# REIS_PCB.net
KiCad netlist of a schematic drawn in Altium Designer
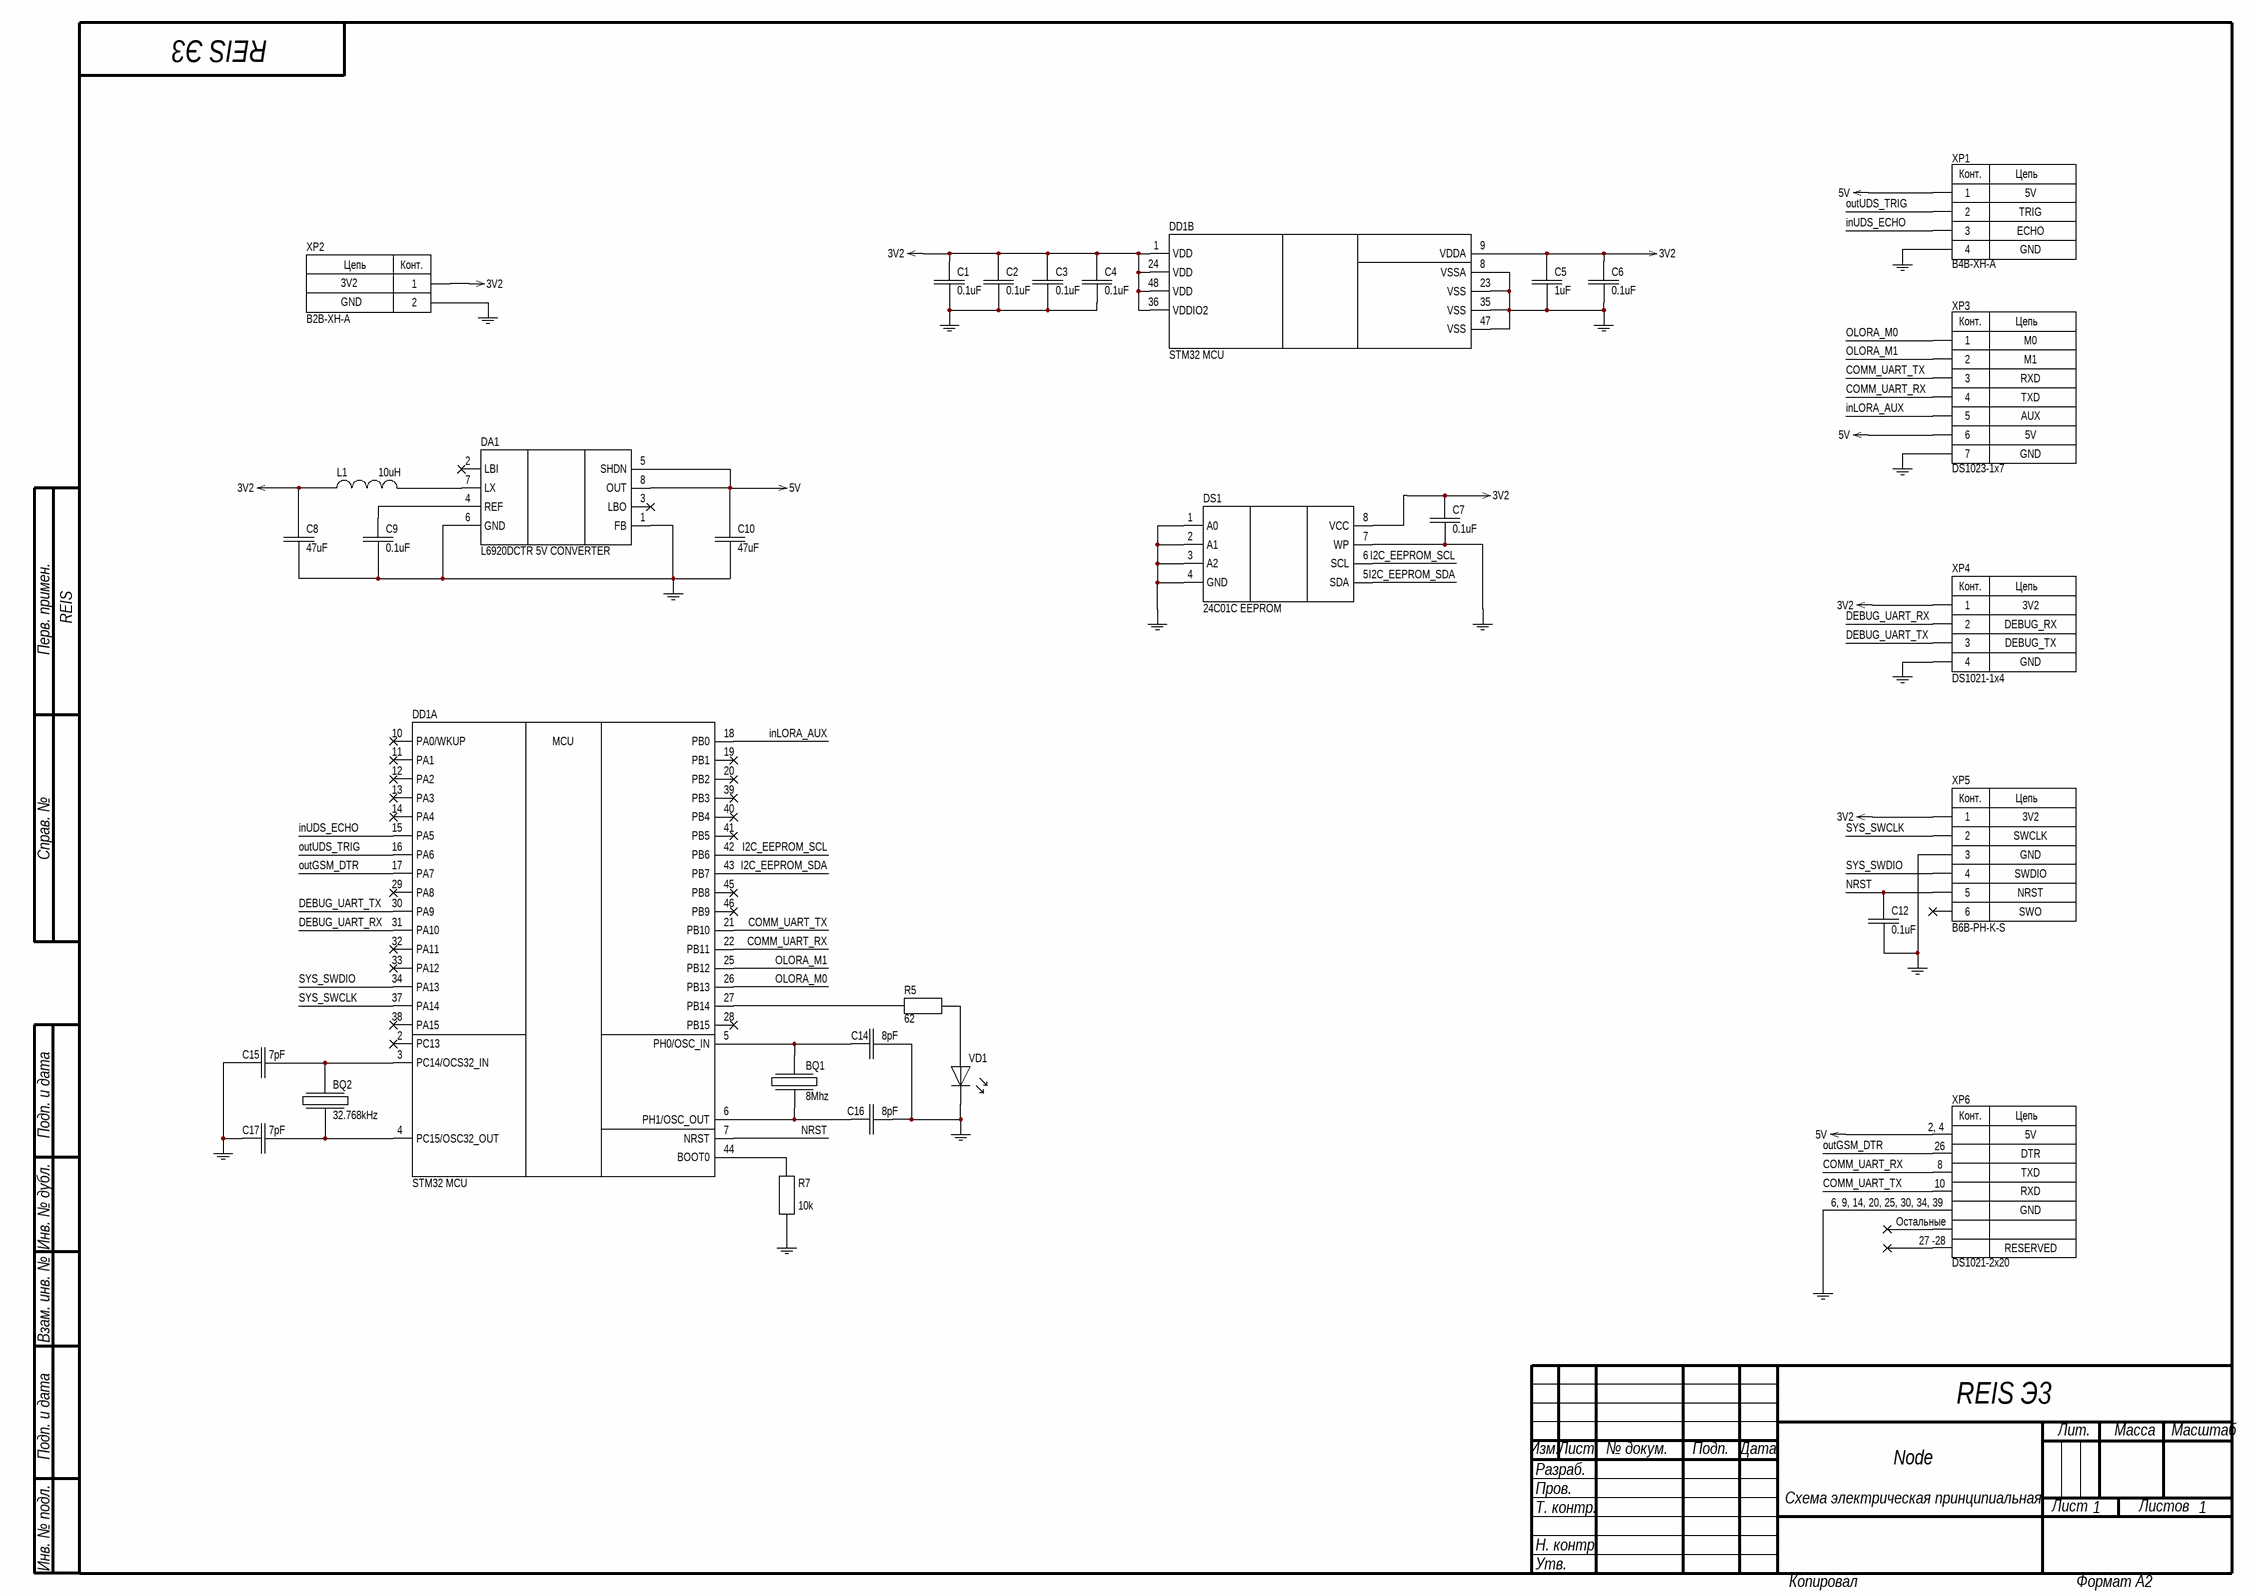
[diagram p0: REIS_PCB.SchDoc]

(export (version "E")
  (design (tool "Eeschema 10.0.6"))
  (components
    (comp (ref "BQ1")
      (value "NX5032GA-8MHz")
      (footprint "NX5032GA-8MHz")
      (description "8MHz resonator")
      (fields (field (name "MANUFACTURER") "NDK") (field (name "FREQUENCY") "8Mhz"))
      (libsource (lib "REIS_PCB") (part "NX5032GA-8MHz"))
    )
    (comp (ref "BQ2")
      (value "NX3215SA-32.768K")
      (footprint "NX3215SA-32.768kHz")
      (description "32.768kHz resonator")
      (fields (field (name "MANUFACTURER") "NDK") (field (name "FREQUENCY") "32.768kHz"))
      (libsource (lib "REIS_PCB") (part "NX3215SA-32.768K"))
    )
    (comp (ref "C1")
      (value "GRM188R71H104JA93D")
      (footprint "0603")
      (description "0.1uF capacitor")
      (fields
        (field (name "MANUFACTURER") "Murata")
        (field (name "CAPACITY") "0.1uF")
        (field (name "VOLTAGE") "50V")
      )
      (libsource (lib "REIS_PCB") (part "GRM188R71H104JA93D"))
    )
    (comp (ref "C2")
      (value "GRM188R71H104JA93D")
      (footprint "0603")
      (description "0.1uF capacitor")
      (fields
        (field (name "MANUFACTURER") "Murata")
        (field (name "CAPACITY") "0.1uF")
        (field (name "VOLTAGE") "50V")
      )
      (libsource (lib "REIS_PCB") (part "GRM188R71H104JA93D"))
    )
    (comp (ref "C3")
      (value "GRM188R71H104JA93D")
      (footprint "0603")
      (description "0.1uF capacitor")
      (fields
        (field (name "MANUFACTURER") "Murata")
        (field (name "CAPACITY") "0.1uF")
        (field (name "VOLTAGE") "50V")
      )
      (libsource (lib "REIS_PCB") (part "GRM188R71H104JA93D"))
    )
    (comp (ref "C4")
      (value "GRM188R71H104JA93D")
      (footprint "0603")
      (description "0.1uF capacitor")
      (fields
        (field (name "MANUFACTURER") "Murata")
        (field (name "CAPACITY") "0.1uF")
        (field (name "VOLTAGE") "50V")
      )
      (libsource (lib "REIS_PCB") (part "GRM188R71H104JA93D"))
    )
    (comp (ref "C5")
      (value "GRM188R71E105KA12D")
      (footprint "0603")
      (description "1uF capacitor")
      (fields
        (field (name "MANUFACTURER") "Murata")
        (field (name "CAPACITY") "1uF")
        (field (name "VOLTAGE") "25V")
      )
      (libsource (lib "REIS_PCB") (part "GRM188R71E105KA12D"))
    )
    (comp (ref "C6")
      (value "GRM188R71H104JA93D")
      (footprint "0603")
      (description "0.1uF capacitor")
      (fields
        (field (name "MANUFACTURER") "Murata")
        (field (name "CAPACITY") "0.1uF")
        (field (name "VOLTAGE") "50V")
      )
      (libsource (lib "REIS_PCB") (part "GRM188R71H104JA93D"))
    )
    (comp (ref "C7")
      (value "GRM188R71H104JA93D")
      (footprint "0603")
      (description "0.1uF capacitor")
      (fields
        (field (name "MANUFACTURER") "Murata")
        (field (name "CAPACITY") "0.1uF")
        (field (name "VOLTAGE") "50V")
      )
      (libsource (lib "REIS_PCB") (part "GRM188R71H104JA93D"))
    )
    (comp (ref "C8")
      (value "GRM319R61E475K")
      (footprint "1206")
      (description "47uF capacitor")
      (fields
        (field (name "MANUFACTURER") "Murata")
        (field (name "CAPACITY") "47uF")
        (field (name "VOLTAGE") "25V")
      )
      (libsource (lib "REIS_PCB") (part "GRM319R61E475K"))
    )
    (comp (ref "C9")
      (value "GRM188R71H104JA93D")
      (footprint "0603")
      (description "0.1uF capacitor")
      (fields
        (field (name "MANUFACTURER") "Murata")
        (field (name "CAPACITY") "0.1uF")
        (field (name "VOLTAGE") "50V")
      )
      (libsource (lib "REIS_PCB") (part "GRM188R71H104JA93D"))
    )
    (comp (ref "C10")
      (value "GRM319R61E475K")
      (footprint "1206")
      (description "47uF capacitor")
      (fields
        (field (name "MANUFACTURER") "Murata")
        (field (name "CAPACITY") "47uF")
        (field (name "VOLTAGE") "25V")
      )
      (libsource (lib "REIS_PCB") (part "GRM319R61E475K"))
    )
    (comp (ref "C12")
      (value "GRM188R71H104JA93D")
      (footprint "0603")
      (description "0.1uF capacitor")
      (fields
        (field (name "MANUFACTURER") "Murata")
        (field (name "CAPACITY") "0.1uF")
        (field (name "VOLTAGE") "50V")
      )
      (libsource (lib "REIS_PCB") (part "GRM188R71H104JA93D"))
    )
    (comp (ref "C14")
      (value "CC0603DRNPO9BN8R0")
      (footprint "0603")
      (description "8pF capacitor")
      (fields
        (field (name "MANUFACTURER") "Yageo")
        (field (name "CAPACITY") "8pF")
        (field (name "VOLTAGE") "50V")
      )
      (libsource (lib "REIS_PCB") (part "CC0603DRNPO9BN8R0"))
    )
    (comp (ref "C15")
      (value "CC0603CRNPO9BN7R0")
      (footprint "0603")
      (description "7pF capacitor")
      (fields
        (field (name "MANUFACTURER") "Yageo")
        (field (name "CAPACITY") "7pF")
        (field (name "VOLTAGE") "50V")
      )
      (libsource (lib "REIS_PCB") (part "CC0603CRNPO9BN7R0"))
    )
    (comp (ref "C16")
      (value "CC0603DRNPO9BN8R0")
      (footprint "0603")
      (description "8pF capacitor")
      (fields
        (field (name "MANUFACTURER") "Yageo")
        (field (name "CAPACITY") "8pF")
        (field (name "VOLTAGE") "50V")
      )
      (libsource (lib "REIS_PCB") (part "CC0603DRNPO9BN8R0"))
    )
    (comp (ref "C17")
      (value "CC0603CRNPO9BN7R0")
      (footprint "0603")
      (description "7pF capacitor")
      (fields
        (field (name "MANUFACTURER") "Yageo")
        (field (name "CAPACITY") "7pF")
        (field (name "VOLTAGE") "50V")
      )
      (libsource (lib "REIS_PCB") (part "CC0603CRNPO9BN7R0"))
    )
    (comp (ref "DA1")
      (value "L6920DCTR 5V CONVERTER")
      (footprint "MSOP")
      (description "Synchronous rectifier step up converter")
      (fields (field (name "MANUFACTURER") "STMicroelectronics"))
      (libsource (lib "REIS_PCB") (part "L6920DCTR"))
    )
    (comp (ref "DD1")
      (value "STM32 MCU")
      (footprint "LQFP48")
      (description "MCU STM32")
      (fields (field (name "MANUFACTURER") "STMicroelectronics"))
      (libsource (lib "REIS_PCB") (part "STM32L051C8T6"))
    )
    (comp (ref "DS1")
      (value "24C01C EEPROM")
      (footprint "SOIC8")
      (description "Serial EEPROM")
      (fields (field (name "MANUFACTURER") "Atmel"))
      (libsource (lib "REIS_PCB") (part "24C01C-SSHM-T"))
    )
    (comp (ref "L1")
      (value "LQH55DN100M")
      (footprint "2220")
      (description "10 uH inductor")
      (fields (field (name "MANUFACTURER") "Murata") (field (name "INDUCTANCE") "10uH"))
      (libsource (lib "REIS_PCB") (part "LQH55DN100M"))
    )
    (comp (ref "R5")
      (value "RC0603JR-0762RL")
      (footprint "0603")
      (description "62Ohm resistor")
      (fields (field (name "MANUFACTURER") "Тайвань") (field (name "RESISTANCE") "62"))
      (libsource (lib "REIS_PCB") (part "RC0603JR-0762RL"))
    )
    (comp (ref "R7")
      (value "RC0603FR-0710KL")
      (footprint "0603")
      (description "10k resistor")
      (fields (field (name "RESISTANCE") "10k"))
      (libsource (lib "REIS_PCB") (part "RC0603FR-0710KL"))
    )
    (comp (ref "VD1")
      (value "GNL-0603EC")
      (footprint "0603LED")
      (description "Red light-emitting diode")
      (fields (field (name "MANUFACTURER") "G-nor"))
      (libsource (lib "REIS_PCB") (part "GNL-0603EC"))
    )
    (comp (ref "XP1")
      (value "B4B-XH-A")
      (footprint "B4B-XH-A")
      (description "Connector 4pin")
      (fields
        (field (name "MANUFACTURER") "JST")
        (field (name "PARAMETER 1") "5V")
        (field (name "PARAMETER 2") "TRIG")
        (field (name "PARAMETER 3") "ECHO")
        (field (name "PARAMETER 4") "GND")
      )
      (libsource (lib "REIS_PCB") (part "B4B-XH-A"))
    )
    (comp (ref "XP2")
      (value "B2B-XH-A")
      (footprint "B2B-XH-A")
      (description "Power connector")
      (fields
        (field (name "MANUFACTURER") "JST")
        (field (name "PARAMETER 1") "3V2")
        (field (name "PARAMETER 2") "GND")
      )
      (libsource (lib "REIS_PCB") (part "B2B-XH-A"))
    )
    (comp (ref "XP3")
      (value "DS1023-1x7")
      (footprint "DS1023-1x7")
      (description "Connector E032 to PBS7_DS1023-1x7")
      (fields
        (field (name "MANUFACTURER") "Connfly")
        (field (name "PARAMETER 1") "M0")
        (field (name "PARAMETER 2") "M1")
        (field (name "PARAMETER 3") "RXD")
        (field (name "PARAMETER 4") "TXD")
        (field (name "PARAMETER 5") "AUX")
        (field (name "PARAMETER 6") "5V")
        (field (name "PARAMETER 7") "GND")
      )
      (libsource (lib "REIS_PCB") (part "DS1023-1x7"))
    )
    (comp (ref "XP4")
      (value "DS1021-1x4")
      (footprint "DS1021-1x4")
      (description "USART connector PLS4_DS1021-1x4")
      (fields
        (field (name "MANUFACTURER") "Connfly")
        (field (name "PARAMETER 1") "3V2")
        (field (name "PARAMETER 2") "DEBUG_RX")
        (field (name "PARAMETER 3") "DEBUG_TX")
        (field (name "PARAMETER 4") "GND")
      )
      (libsource (lib "REIS_PCB") (part "DS1021-1x4"))
    )
    (comp (ref "XP5")
      (value "B6B-PH-K-S")
      (footprint "B6B-PH-K-S")
      (description "SWDIO connector")
      (fields
        (field (name "MANUFACTURER") "JST")
        (field (name "PARAMETER 1") "3V2")
        (field (name "PARAMETER 2") "SWCLK")
        (field (name "PARAMETER 3") "GND")
        (field (name "PARAMETER 4") "SWDIO")
        (field (name "PARAMETER 5") "NRST")
        (field (name "PARAMETER 6") "SWO")
      )
      (libsource (lib "REIS_PCB") (part "B6B-PH-K-S"))
    )
    (comp (ref "XP6")
      (value "DS1021-2x20")
      (footprint "DS1021-2x20")
      (description "Connector SIM7000E")
      (fields
        (field (name "MANUFACTURER") "Connfly")
        (field (name "PARAMETER 1") "5V")
        (field (name "PARAMETER 2") "DTR")
        (field (name "PARAMETER 3") "TXD")
        (field (name "PARAMETER 4") "RXD")
        (field (name "PARAMETER 5") "GND")
        (field (name "PARAMETER 7") "RESERVED")
      )
      (libsource (lib "REIS_PCB") (part "DS1021-2x20"))
    )
  )
  (nets
    (net (code "1") (name "/COMM_UART_RX") (class "Default")
      (node (ref "DD1") (pin "22") (pinfunction "PB11_22") (pintype "passive"))
      (node (ref "XP3") (pin "4") (pinfunction "4_4") (pintype "passive"))
      (node (ref "XP6") (pin "8") (pinfunction "3_8") (pintype "passive"))
    )
    (net (code "2") (name "/COMM_UART_TX") (class "Default")
      (node (ref "DD1") (pin "21") (pinfunction "PB10_21") (pintype "passive"))
      (node (ref "XP3") (pin "3") (pinfunction "3_3") (pintype "passive"))
      (node (ref "XP6") (pin "10") (pinfunction "4_10") (pintype "passive"))
    )
    (net (code "3") (name "/DEBUG_UART_RX") (class "Default")
      (node (ref "DD1") (pin "31") (pinfunction "PA10_31") (pintype "passive"))
      (node (ref "XP4") (pin "2") (pinfunction "2_2") (pintype "passive"))
    )
    (net (code "4") (name "/DEBUG_UART_TX") (class "Default")
      (node (ref "DD1") (pin "30") (pinfunction "PA9_30") (pintype "passive"))
      (node (ref "XP4") (pin "3") (pinfunction "3_3") (pintype "passive"))
    )
    (net (code "5") (name "/I2C_EEPROM_SCL") (class "Default")
      (node (ref "DD1") (pin "42") (pinfunction "PB6_42") (pintype "passive"))
      (node (ref "DS1") (pin "6") (pinfunction "SCL_6") (pintype "passive"))
    )
    (net (code "6") (name "/I2C_EEPROM_SDA") (class "Default")
      (node (ref "DD1") (pin "43") (pinfunction "PB7_43") (pintype "passive"))
      (node (ref "DS1") (pin "5") (pinfunction "SDA_5") (pintype "passive"))
    )
    (net (code "7") (name "/NRST") (class "Default")
      (node (ref "C12") (pin "2") (pinfunction "2_2") (pintype "passive"))
      (node (ref "DD1") (pin "7") (pinfunction "NRST_7") (pintype "passive"))
      (node (ref "XP5") (pin "5") (pinfunction "5_5") (pintype "passive"))
    )
    (net (code "8") (name "/OLORA_M0") (class "Default")
      (node (ref "DD1") (pin "26") (pinfunction "PB13_26") (pintype "passive"))
      (node (ref "XP3") (pin "1") (pinfunction "1_1") (pintype "passive"))
    )
    (net (code "9") (name "/OLORA_M1") (class "Default")
      (node (ref "DD1") (pin "25") (pinfunction "PB12_25") (pintype "passive"))
      (node (ref "XP3") (pin "2") (pinfunction "2_2") (pintype "passive"))
    )
    (net (code "10") (name "/SYS_SWCLK") (class "Default")
      (node (ref "DD1") (pin "37") (pinfunction "PA14_37") (pintype "passive"))
      (node (ref "XP5") (pin "2") (pinfunction "2_2") (pintype "passive"))
    )
    (net (code "11") (name "/SYS_SWDIO") (class "Default")
      (node (ref "DD1") (pin "34") (pinfunction "PA13_34") (pintype "passive"))
      (node (ref "XP5") (pin "4") (pinfunction "4_4") (pintype "passive"))
    )
    (net (code "12") (name "/inLORA_AUX") (class "Default")
      (node (ref "DD1") (pin "18") (pinfunction "PB0_18") (pintype "passive"))
      (node (ref "XP3") (pin "5") (pinfunction "5_5") (pintype "passive"))
    )
    (net (code "13") (name "/inUDS_ECHO") (class "Default")
      (node (ref "DD1") (pin "15") (pinfunction "PA5_15") (pintype "passive"))
      (node (ref "XP1") (pin "3") (pinfunction "3_3") (pintype "passive"))
    )
    (net (code "14") (name "/outGSM_DTR") (class "Default")
      (node (ref "DD1") (pin "17") (pinfunction "PA7_17") (pintype "passive"))
      (node (ref "XP6") (pin "26") (pinfunction "2_26") (pintype "passive"))
    )
    (net (code "15") (name "/outUDS_TRIG") (class "Default")
      (node (ref "DD1") (pin "16") (pinfunction "PA6_16") (pintype "passive"))
      (node (ref "XP1") (pin "2") (pinfunction "2_2") (pintype "passive"))
    )
    (net (code "16") (name "3V2") (class "Default")
      (node (ref "C1") (pin "2") (pinfunction "2_2") (pintype "passive"))
      (node (ref "C2") (pin "2") (pinfunction "2_2") (pintype "passive"))
      (node (ref "C3") (pin "2") (pinfunction "2_2") (pintype "passive"))
      (node (ref "C4") (pin "2") (pinfunction "2_2") (pintype "passive"))
      (node (ref "C5") (pin "2") (pinfunction "2_2") (pintype "passive"))
      (node (ref "C6") (pin "2") (pinfunction "2_2") (pintype "passive"))
      (node (ref "C7") (pin "2") (pinfunction "2_2") (pintype "passive"))
      (node (ref "C8") (pin "2") (pinfunction "2_2") (pintype "passive"))
      (node (ref "DD1") (pin "1") (pinfunction "VDD_1") (pintype "passive"))
      (node (ref "DD1") (pin "24") (pinfunction "VDD_24") (pintype "passive"))
      (node (ref "DD1") (pin "36") (pinfunction "VDDIO2_36") (pintype "passive"))
      (node (ref "DD1") (pin "48") (pinfunction "VDD_48") (pintype "passive"))
      (node (ref "DD1") (pin "9") (pinfunction "VDDA_9") (pintype "passive"))
      (node (ref "DS1") (pin "8") (pinfunction "VCC_8") (pintype "passive"))
      (node (ref "L1") (pin "1") (pinfunction "1_1") (pintype "passive"))
      (node (ref "XP2") (pin "1") (pinfunction "1_1") (pintype "passive"))
      (node (ref "XP4") (pin "1") (pinfunction "1_1") (pintype "passive"))
      (node (ref "XP5") (pin "1") (pinfunction "1_1") (pintype "passive"))
    )
    (net (code "17") (name "5V") (class "Default")
      (node (ref "C10") (pin "2") (pinfunction "2_2") (pintype "passive"))
      (node (ref "DA1") (pin "5") (pinfunction "SHDN_5") (pintype "passive"))
      (node (ref "DA1") (pin "8") (pinfunction "OUT_8") (pintype "passive"))
      (node (ref "XP1") (pin "1") (pinfunction "1_1") (pintype "passive"))
      (node (ref "XP3") (pin "6") (pinfunction "6_6") (pintype "passive"))
      (node (ref "XP6") (pin "2") (pinfunction "1_2") (pintype "passive"))
    )
    (net (code "18") (name "GND") (class "Default")
      (node (ref "C1") (pin "1") (pinfunction "1_1") (pintype "passive"))
      (node (ref "C10") (pin "1") (pinfunction "1_1") (pintype "passive"))
      (node (ref "C12") (pin "1") (pinfunction "1_1") (pintype "passive"))
      (node (ref "C14") (pin "1") (pinfunction "1_1") (pintype "passive"))
      (node (ref "C15") (pin "1") (pinfunction "1_1") (pintype "passive"))
      (node (ref "C16") (pin "1") (pinfunction "1_1") (pintype "passive"))
      (node (ref "C17") (pin "1") (pinfunction "1_1") (pintype "passive"))
      (node (ref "C2") (pin "1") (pinfunction "1_1") (pintype "passive"))
      (node (ref "C3") (pin "1") (pinfunction "1_1") (pintype "passive"))
      (node (ref "C4") (pin "1") (pinfunction "1_1") (pintype "passive"))
      (node (ref "C5") (pin "1") (pinfunction "1_1") (pintype "passive"))
      (node (ref "C6") (pin "1") (pinfunction "1_1") (pintype "passive"))
      (node (ref "C7") (pin "1") (pinfunction "1_1") (pintype "passive"))
      (node (ref "C8") (pin "1") (pinfunction "1_1") (pintype "passive"))
      (node (ref "C9") (pin "1") (pinfunction "1_1") (pintype "passive"))
      (node (ref "DA1") (pin "1") (pinfunction "FB_1") (pintype "passive"))
      (node (ref "DA1") (pin "6") (pinfunction "GND_6") (pintype "passive"))
      (node (ref "DD1") (pin "23") (pinfunction "VSS_23") (pintype "passive"))
      (node (ref "DD1") (pin "35") (pinfunction "VSS_35") (pintype "passive"))
      (node (ref "DD1") (pin "47") (pinfunction "VSS_47") (pintype "passive"))
      (node (ref "DD1") (pin "8") (pinfunction "VSSA_8") (pintype "passive"))
      (node (ref "DS1") (pin "1") (pinfunction "A0_1") (pintype "passive"))
      (node (ref "DS1") (pin "2") (pinfunction "A1_2") (pintype "passive"))
      (node (ref "DS1") (pin "3") (pinfunction "A2_3") (pintype "passive"))
      (node (ref "DS1") (pin "4") (pinfunction "GND_4") (pintype "passive"))
      (node (ref "DS1") (pin "7") (pinfunction "WP_7") (pintype "passive"))
      (node (ref "R7") (pin "1") (pinfunction "1_1") (pintype "passive"))
      (node (ref "VD1") (pin "2") (pinfunction "2_2") (pintype "passive"))
      (node (ref "XP1") (pin "4") (pinfunction "4_4") (pintype "passive"))
      (node (ref "XP2") (pin "2") (pinfunction "2_2") (pintype "passive"))
      (node (ref "XP3") (pin "7") (pinfunction "7_7") (pintype "passive"))
      (node (ref "XP4") (pin "4") (pinfunction "4_4") (pintype "passive"))
      (node (ref "XP5") (pin "3") (pinfunction "3_3") (pintype "passive"))
      (node (ref "XP6") (pin "6") (pinfunction "5_6") (pintype "passive"))
    )
    (net (code "19") (name "Net-(DA1-LX)") (class "Default")
      (node (ref "DA1") (pin "7") (pinfunction "LX_7") (pintype "passive"))
      (node (ref "L1") (pin "2") (pinfunction "2_2") (pintype "passive"))
    )
    (net (code "20") (name "Net-(DA1-REF)") (class "Default")
      (node (ref "C9") (pin "2") (pinfunction "2_2") (pintype "passive"))
      (node (ref "DA1") (pin "4") (pinfunction "REF_4") (pintype "passive"))
    )
    (net (code "21") (name "Net-(DD1A-BOOT0)") (class "Default")
      (node (ref "DD1") (pin "44") (pinfunction "BOOT0_44") (pintype "passive"))
      (node (ref "R7") (pin "2") (pinfunction "2_2") (pintype "passive"))
    )
    (net (code "22") (name "Net-(DD1A-PB14)") (class "Default")
      (node (ref "DD1") (pin "27") (pinfunction "PB14_27") (pintype "passive"))
      (node (ref "R5") (pin "2") (pinfunction "2_2") (pintype "passive"))
    )
    (net (code "23") (name "Net-(DD1A-PC14{slash}OCS32_IN)") (class "Default")
      (node (ref "BQ2") (pin "2") (pinfunction "2_2") (pintype "passive"))
      (node (ref "C15") (pin "2") (pinfunction "2_2") (pintype "passive"))
      (node (ref "DD1") (pin "3") (pinfunction "PC14/OCS32_IN_3") (pintype "passive"))
    )
    (net (code "24") (name "Net-(DD1A-PC15{slash}OSC32_OUT)") (class "Default")
      (node (ref "BQ2") (pin "1") (pinfunction "1_1") (pintype "passive"))
      (node (ref "C17") (pin "2") (pinfunction "2_2") (pintype "passive"))
      (node (ref "DD1") (pin "4") (pinfunction "PC15/OSC32_OUT_4") (pintype "passive"))
    )
    (net (code "25") (name "Net-(DD1A-PH0{slash}OSC_IN)") (class "Default")
      (node (ref "BQ1") (pin "2") (pinfunction "2_2") (pintype "passive"))
      (node (ref "C14") (pin "2") (pinfunction "2_2") (pintype "passive"))
      (node (ref "DD1") (pin "5") (pinfunction "PH0/OSC_IN_5") (pintype "passive"))
    )
    (net (code "26") (name "Net-(DD1A-PH1{slash}OSC_OUT)") (class "Default")
      (node (ref "BQ1") (pin "1") (pinfunction "1_1") (pintype "passive"))
      (node (ref "C16") (pin "2") (pinfunction "2_2") (pintype "passive"))
      (node (ref "DD1") (pin "6") (pinfunction "PH1/OSC_OUT_6") (pintype "passive"))
    )
    (net (code "27") (name "Net-(R5-Pad1)") (class "Default")
      (node (ref "R5") (pin "1") (pinfunction "1_1") (pintype "passive"))
      (node (ref "VD1") (pin "1") (pinfunction "1_1") (pintype "passive"))
    )
    (net (code "28") (name "unconnected-(DA1-LBI-Pad2)") (class "Default")
      (node (ref "DA1") (pin "2") (pinfunction "LBI_2") (pintype "passive+no_connect"))
    )
    (net (code "29") (name "unconnected-(DA1-LBO-Pad3)") (class "Default")
      (node (ref "DA1") (pin "3") (pinfunction "LBO_3") (pintype "passive+no_connect"))
    )
    (net (code "30") (name "unconnected-(DD1A-PA0{slash}WKUP-Pad10)") (class "Default")
      (node (ref "DD1") (pin "10") (pinfunction "PA0/WKUP_10") (pintype "passive+no_connect"))
    )
    (net (code "31") (name "unconnected-(DD1A-PA1-Pad11)") (class "Default")
      (node (ref "DD1") (pin "11") (pinfunction "PA1_11") (pintype "passive+no_connect"))
    )
    (net (code "32") (name "unconnected-(DD1A-PA2-Pad12)") (class "Default")
      (node (ref "DD1") (pin "12") (pinfunction "PA2_12") (pintype "passive+no_connect"))
    )
    (net (code "33") (name "unconnected-(DD1A-PA3-Pad13)") (class "Default")
      (node (ref "DD1") (pin "13") (pinfunction "PA3_13") (pintype "passive+no_connect"))
    )
    (net (code "34") (name "unconnected-(DD1A-PA4-Pad14)") (class "Default")
      (node (ref "DD1") (pin "14") (pinfunction "PA4_14") (pintype "passive+no_connect"))
    )
    (net (code "35") (name "unconnected-(DD1A-PA8-Pad29)") (class "Default")
      (node (ref "DD1") (pin "29") (pinfunction "PA8_29") (pintype "passive+no_connect"))
    )
    (net (code "36") (name "unconnected-(DD1A-PA11-Pad32)") (class "Default")
      (node (ref "DD1") (pin "32") (pinfunction "PA11_32") (pintype "passive+no_connect"))
    )
    (net (code "37") (name "unconnected-(DD1A-PA12-Pad33)") (class "Default")
      (node (ref "DD1") (pin "33") (pinfunction "PA12_33") (pintype "passive+no_connect"))
    )
    (net (code "38") (name "unconnected-(DD1A-PA15-Pad38)") (class "Default")
      (node (ref "DD1") (pin "38") (pinfunction "PA15_38") (pintype "passive+no_connect"))
    )
    (net (code "39") (name "unconnected-(DD1A-PB1-Pad19)") (class "Default")
      (node (ref "DD1") (pin "19") (pinfunction "PB1_19") (pintype "passive+no_connect"))
    )
    (net (code "40") (name "unconnected-(DD1A-PB2-Pad20)") (class "Default")
      (node (ref "DD1") (pin "20") (pinfunction "PB2_20") (pintype "passive+no_connect"))
    )
    (net (code "41") (name "unconnected-(DD1A-PB3-Pad39)") (class "Default")
      (node (ref "DD1") (pin "39") (pinfunction "PB3_39") (pintype "passive+no_connect"))
    )
    (net (code "42") (name "unconnected-(DD1A-PB4-Pad40)") (class "Default")
      (node (ref "DD1") (pin "40") (pinfunction "PB4_40") (pintype "passive+no_connect"))
    )
    (net (code "43") (name "unconnected-(DD1A-PB5-Pad41)") (class "Default")
      (node (ref "DD1") (pin "41") (pinfunction "PB5_41") (pintype "passive+no_connect"))
    )
    (net (code "44") (name "unconnected-(DD1A-PB8-Pad45)") (class "Default")
      (node (ref "DD1") (pin "45") (pinfunction "PB8_45") (pintype "passive+no_connect"))
    )
    (net (code "45") (name "unconnected-(DD1A-PB9-Pad46)") (class "Default")
      (node (ref "DD1") (pin "46") (pinfunction "PB9_46") (pintype "passive+no_connect"))
    )
    (net (code "46") (name "unconnected-(DD1A-PB15-Pad28)") (class "Default")
      (node (ref "DD1") (pin "28") (pinfunction "PB15_28") (pintype "passive+no_connect"))
    )
    (net (code "47") (name "unconnected-(DD1A-PC13-Pad2)") (class "Default")
      (node (ref "DD1") (pin "2") (pinfunction "PC13_2") (pintype "passive+no_connect"))
    )
    (net (code "48") (name "unconnected-(XP5-Pad6)") (class "Default")
      (node (ref "XP5") (pin "6") (pinfunction "6_6") (pintype "passive+no_connect"))
    )
    (net (code "49") (name "unconnected-(XP6-6-Pad7)") (class "Default")
      (node (ref "XP6") (pin "7") (pinfunction "6_7") (pintype "passive+no_connect"))
    )
    (net (code "50") (name "unconnected-(XP6-7-Pad27)") (class "Default")
      (node (ref "XP6") (pin "27") (pinfunction "7_27") (pintype "passive+no_connect"))
    )
  )
)
